# current_sense.net
KiCad netlist of a schematic drawn in Altium Designer
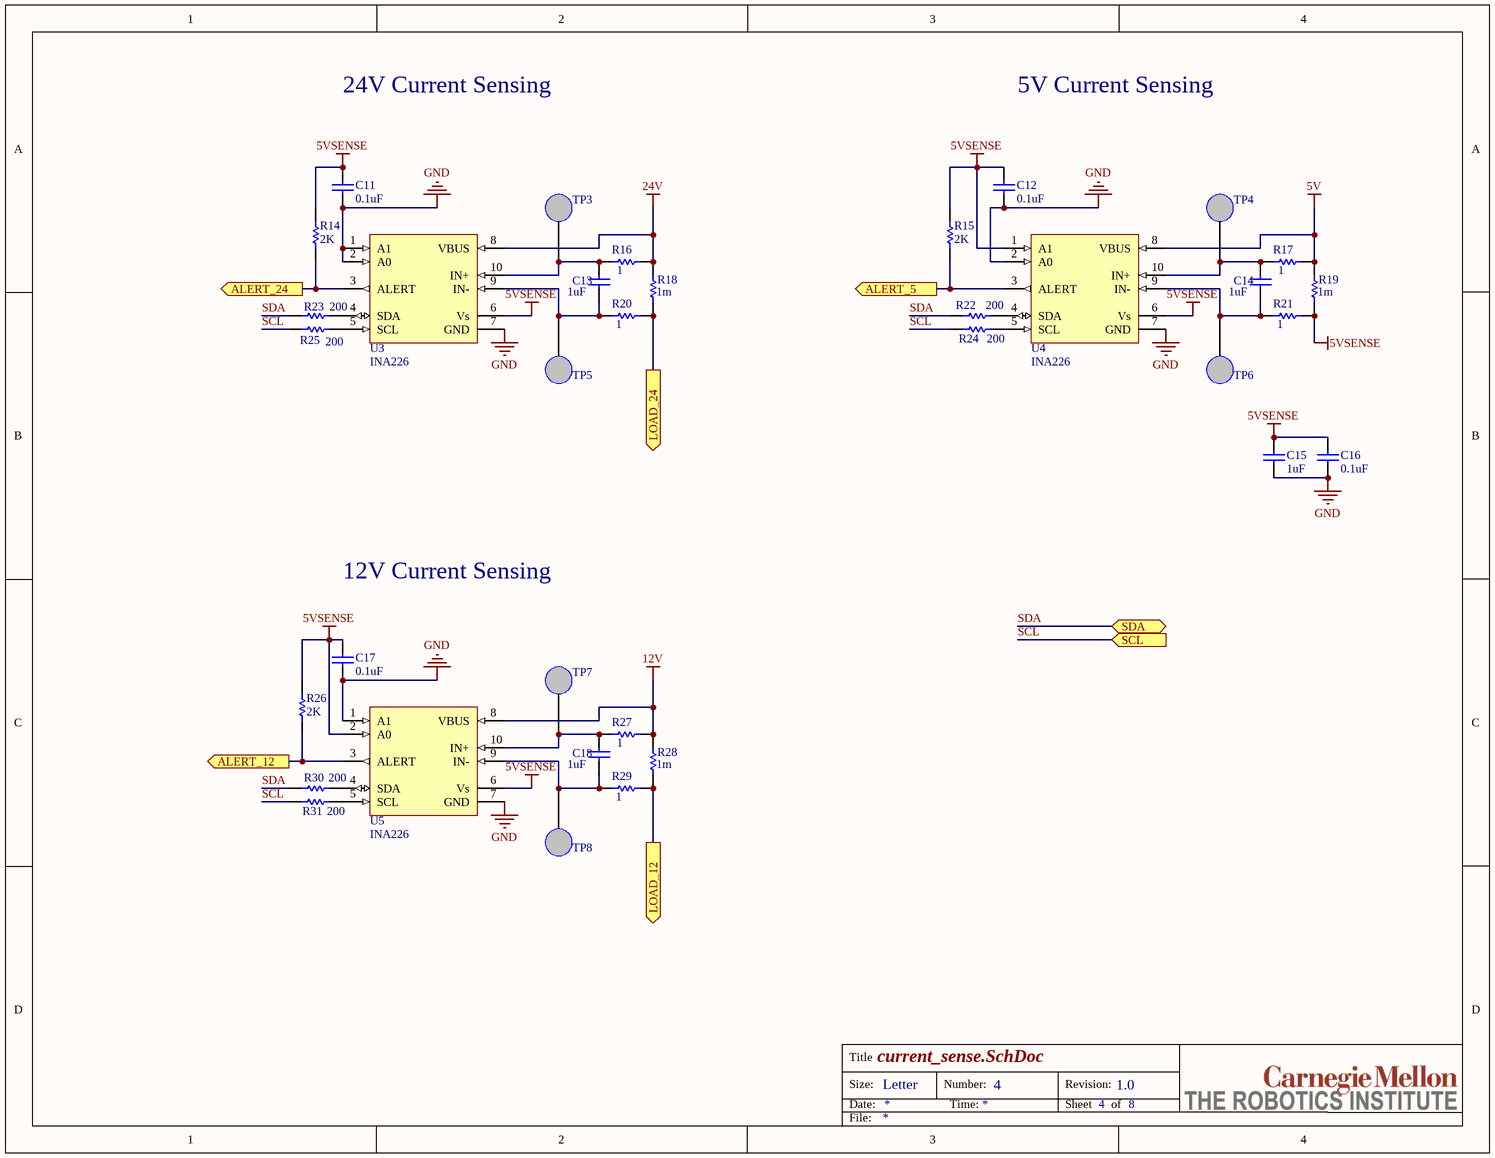
[diagram p0: current_sense.SchDoc]

(export (version "E")
  (design (tool "Eeschema 10.0.6"))
  (components
    (comp (ref "C11")
      (value "0.1uF")
      (footprint "CAPC1608N")
      (description "Capacitor")
      (fields
        (field (name "MANUFACTURER") "Murata Electronics North America")
        (field (name "MANUFACTURER PART NUMBER") "GRM188R71H104JA93D")
        (field (name "PUBLISHER") "Altium Limited")
      )
      (libsource (lib "Miscellaneous Devices") (part "Cap"))
    )
    (comp (ref "C12")
      (value "0.1uF")
      (footprint "CAPC1608N")
      (description "Capacitor")
      (fields
        (field (name "MANUFACTURER") "Murata Electronics North America")
        (field (name "MANUFACTURER PART NUMBER") "GRM188R71H104JA93D")
        (field (name "PUBLISHER") "Altium Limited")
      )
      (libsource (lib "Miscellaneous Devices") (part "Cap"))
    )
    (comp (ref "C13")
      (value "1uF")
      (footprint "CAPC1608N")
      (description "Capacitor")
      (fields
        (field (name "MANUFACTURER") "Murata Electronics North America")
        (field (name "MANUFACTURER PART NUMBER") "GRM188R61H105KAALD")
        (field (name "PUBLISHER") "Altium Limited")
      )
      (libsource (lib "Miscellaneous Devices") (part "Cap"))
    )
    (comp (ref "C14")
      (value "1uF")
      (footprint "CAPC1608N")
      (description "Capacitor")
      (fields
        (field (name "MANUFACTURER") "Murata Electronics North America")
        (field (name "MANUFACTURER PART NUMBER") "GRM188R61H105KAALD")
        (field (name "PUBLISHER") "Altium Limited")
      )
      (libsource (lib "Miscellaneous Devices") (part "Cap"))
    )
    (comp (ref "C15")
      (value "1uF")
      (footprint "CAPC1608N")
      (description "Capacitor")
      (fields
        (field (name "MANUFACTURER") "Murata Electronics North America")
        (field (name "MANUFACTURER PART NUMBER") "GRM188R61H105KAALD")
        (field (name "PUBLISHER") "Altium Limited")
      )
      (libsource (lib "Miscellaneous Devices") (part "Cap"))
    )
    (comp (ref "C16")
      (value "0.1uF")
      (footprint "CAPC1608N")
      (description "Capacitor")
      (fields
        (field (name "MANUFACTURER") "Murata Electronics North America")
        (field (name "MANUFACTURER PART NUMBER") "GRM188R71H104JA93D")
        (field (name "PUBLISHER") "Altium Limited")
      )
      (libsource (lib "Miscellaneous Devices") (part "Cap"))
    )
    (comp (ref "C17")
      (value "0.1uF")
      (footprint "CAPC1608N")
      (description "Capacitor")
      (fields
        (field (name "MANUFACTURER") "Murata Electronics North America")
        (field (name "MANUFACTURER PART NUMBER") "GRM188R71H104JA93D")
        (field (name "PUBLISHER") "Altium Limited")
      )
      (libsource (lib "Miscellaneous Devices") (part "Cap"))
    )
    (comp (ref "C18")
      (value "1uF")
      (footprint "CAPC1608N")
      (description "Capacitor")
      (fields
        (field (name "MANUFACTURER") "Murata Electronics North America")
        (field (name "MANUFACTURER PART NUMBER") "GRM188R61H105KAALD")
        (field (name "PUBLISHER") "Altium Limited")
      )
      (libsource (lib "Miscellaneous Devices") (part "Cap"))
    )
    (comp (ref "R14")
      (value "2K")
      (footprint "RESC1608N")
      (description "Resistor")
      (fields
        (field (name "MANUFACTURER") "Yageo")
        (field (name "MANUFACTURER PART NUMBER") "RC0603JR-072KL")
        (field (name "PUBLISHER") "Altium Limited")
      )
      (libsource (lib "Miscellaneous Devices") (part "Res1"))
    )
    (comp (ref "R15")
      (value "2K")
      (footprint "RESC1608N")
      (description "Resistor")
      (fields
        (field (name "MANUFACTURER") "Yageo")
        (field (name "MANUFACTURER PART NUMBER") "RC0603JR-072KL")
        (field (name "PUBLISHER") "Altium Limited")
      )
      (libsource (lib "Miscellaneous Devices") (part "Res1"))
    )
    (comp (ref "R16")
      (value "1")
      (footprint "RESC1608N")
      (description "Resistor")
      (fields
        (field (name "MANUFACTURER") "Yageo")
        (field (name "MANUFACTURER PART NUMBER") "RC0603FR-071RL")
        (field (name "PUBLISHER") "Altium Limited")
      )
      (libsource (lib "Miscellaneous Devices") (part "Res1"))
    )
    (comp (ref "R17")
      (value "1")
      (footprint "RESC1608N")
      (description "Resistor")
      (fields
        (field (name "MANUFACTURER") "Yageo")
        (field (name "MANUFACTURER PART NUMBER") "RC0603FR-071RL")
        (field (name "PUBLISHER") "Altium Limited")
      )
      (libsource (lib "Miscellaneous Devices") (part "Res1"))
    )
    (comp (ref "R18")
      (value "1m")
      (footprint "RES5931")
      (description "Resistor")
      (fields
        (field (name "MANUFACTURER") "Rohm Semiconductor")
        (field (name "MANUFACTURER PART NUMBER") "PSR500HTQFH1L00")
        (field (name "PUBLISHER") "Altium Limited")
      )
      (libsource (lib "Miscellaneous Devices") (part "Res1"))
    )
    (comp (ref "R19")
      (value "1m")
      (footprint "RESC3225N")
      (description "Resistor")
      (fields
        (field (name "MANUFACTURER") "Rohm Semiconductor")
        (field (name "MANUFACTURER PART NUMBER") "PMR25HZPFV1L00")
        (field (name "PUBLISHER") "Altium Limited")
      )
      (libsource (lib "Miscellaneous Devices") (part "Res1"))
    )
    (comp (ref "R20")
      (value "1")
      (footprint "RESC1608N")
      (description "Resistor")
      (fields
        (field (name "MANUFACTURER") "Yageo")
        (field (name "MANUFACTURER PART NUMBER") "RC0603FR-071RL")
        (field (name "PUBLISHER") "Altium Limited")
      )
      (libsource (lib "Miscellaneous Devices") (part "Res1"))
    )
    (comp (ref "R21")
      (value "1")
      (footprint "RESC1608N")
      (description "Resistor")
      (fields
        (field (name "MANUFACTURER") "Yageo")
        (field (name "MANUFACTURER PART NUMBER") "RC0603FR-071RL")
        (field (name "PUBLISHER") "Altium Limited")
      )
      (libsource (lib "Miscellaneous Devices") (part "Res1"))
    )
    (comp (ref "R22")
      (value "200")
      (footprint "RESC1608N")
      (description "Resistor")
      (fields
        (field (name "MANUFACTURER") "Yageo")
        (field (name "MANUFACTURER PART NUMBER") "RC0603JR-07200RL")
        (field (name "PUBLISHER") "Altium Limited")
      )
      (libsource (lib "Miscellaneous Devices") (part "Res1"))
    )
    (comp (ref "R23")
      (value "200")
      (footprint "RESC1608N")
      (description "Resistor")
      (fields
        (field (name "MANUFACTURER") "Yageo")
        (field (name "MANUFACTURER PART NUMBER") "RC0603JR-07200RL")
        (field (name "PUBLISHER") "Altium Limited")
      )
      (libsource (lib "Miscellaneous Devices") (part "Res1"))
    )
    (comp (ref "R24")
      (value "200")
      (footprint "RESC1608N")
      (description "Resistor")
      (fields
        (field (name "MANUFACTURER") "Yageo")
        (field (name "MANUFACTURER PART NUMBER") "RC0603JR-07200RL")
        (field (name "PUBLISHER") "Altium Limited")
      )
      (libsource (lib "Miscellaneous Devices") (part "Res1"))
    )
    (comp (ref "R25")
      (value "200")
      (footprint "RESC1608N")
      (description "Resistor")
      (fields
        (field (name "MANUFACTURER") "Yageo")
        (field (name "MANUFACTURER PART NUMBER") "RC0603JR-07200RL")
        (field (name "PUBLISHER") "Altium Limited")
      )
      (libsource (lib "Miscellaneous Devices") (part "Res1"))
    )
    (comp (ref "R26")
      (value "2K")
      (footprint "RESC1608N")
      (description "Resistor")
      (fields
        (field (name "MANUFACTURER") "Yageo")
        (field (name "MANUFACTURER PART NUMBER") "RC0603JR-072KL")
        (field (name "PUBLISHER") "Altium Limited")
      )
      (libsource (lib "Miscellaneous Devices") (part "Res1"))
    )
    (comp (ref "R27")
      (value "1")
      (footprint "RESC1608N")
      (description "Resistor")
      (fields
        (field (name "MANUFACTURER") "Yageo")
        (field (name "MANUFACTURER PART NUMBER") "RC0603FR-071RL")
        (field (name "PUBLISHER") "Altium Limited")
      )
      (libsource (lib "Miscellaneous Devices") (part "Res1"))
    )
    (comp (ref "R28")
      (value "1m")
      (footprint "RESC3225N")
      (description "Resistor")
      (fields
        (field (name "MANUFACTURER") "Rohm Semiconductor")
        (field (name "MANUFACTURER PART NUMBER") "PMR25HZPFV1L00")
        (field (name "PUBLISHER") "Altium Limited")
      )
      (libsource (lib "Miscellaneous Devices") (part "Res1"))
    )
    (comp (ref "R29")
      (value "1")
      (footprint "RESC1608N")
      (description "Resistor")
      (fields
        (field (name "MANUFACTURER") "Yageo")
        (field (name "MANUFACTURER PART NUMBER") "RC0603FR-071RL")
        (field (name "PUBLISHER") "Altium Limited")
      )
      (libsource (lib "Miscellaneous Devices") (part "Res1"))
    )
    (comp (ref "R30")
      (value "200")
      (footprint "RESC1608N")
      (description "Resistor")
      (fields
        (field (name "MANUFACTURER") "Yageo")
        (field (name "MANUFACTURER PART NUMBER") "RC0603JR-07200RL")
        (field (name "PUBLISHER") "Altium Limited")
      )
      (libsource (lib "Miscellaneous Devices") (part "Res1"))
    )
    (comp (ref "R31")
      (value "200")
      (footprint "RESC1608N")
      (description "Resistor")
      (fields
        (field (name "MANUFACTURER") "Yageo")
        (field (name "MANUFACTURER PART NUMBER") "RC0603JR-07200RL")
        (field (name "PUBLISHER") "Altium Limited")
      )
      (libsource (lib "Miscellaneous Devices") (part "Res1"))
    )
    (comp (ref "TP3")
      (value "LOAD")
      (footprint "TestPoint")
      (description "Test Point")
      (libsource (lib "common") (part "Ring_Terminal"))
    )
    (comp (ref "TP4")
      (value "SUPPLY")
      (footprint "TestPoint")
      (description "Test Point")
      (libsource (lib "common") (part "Ring_Terminal"))
    )
    (comp (ref "TP5")
      (value "SUPPLY")
      (footprint "TestPoint")
      (description "Test Point")
      (libsource (lib "common") (part "Ring_Terminal"))
    )
    (comp (ref "TP6")
      (value "LOAD")
      (footprint "TestPoint")
      (description "Test Point")
      (libsource (lib "common") (part "Ring_Terminal"))
    )
    (comp (ref "TP7")
      (value "SUPPLY")
      (footprint "TestPoint")
      (description "Test Point")
      (libsource (lib "common") (part "Ring_Terminal"))
    )
    (comp (ref "TP8")
      (value "LOAD")
      (footprint "TestPoint")
      (description "Test Point")
      (libsource (lib "common") (part "Ring_Terminal"))
    )
    (comp (ref "U3")
      (value "INA226")
      (footprint "10-VSSOP")
      (description "Current Shunt Monitor - I2C Interface")
      (fields
        (field (name "MANUFACTURER") "Texas Instruments")
        (field (name "MANUFACTURER PART NUMBER") "INA226AIDGSR")
      )
      (libsource (lib "common") (part "INA226"))
    )
    (comp (ref "U4")
      (value "INA226")
      (footprint "10-VSSOP")
      (description "Current Shunt Monitor - I2C Interface")
      (fields
        (field (name "MANUFACTURER") "Texas Instruments")
        (field (name "MANUFACTURER PART NUMBER") "INA226AIDGSR")
      )
      (libsource (lib "common") (part "INA226"))
    )
    (comp (ref "U5")
      (value "INA226")
      (footprint "10-VSSOP")
      (description "Current Shunt Monitor - I2C Interface")
      (fields
        (field (name "MANUFACTURER") "Texas Instruments")
        (field (name "MANUFACTURER PART NUMBER") "INA226AIDGSR")
      )
      (libsource (lib "common") (part "INA226"))
    )
  )
  (nets
    (net (code "1") (name "/ALERT_5") (class "Default")
      (node (ref "R15") (pin "2") (pinfunction "2_2") (pintype "passive"))
      (node (ref "U4") (pin "3") (pinfunction "ALERT_3") (pintype "output"))
    )
    (net (code "2") (name "/ALERT_12") (class "Default")
      (node (ref "R26") (pin "2") (pinfunction "2_2") (pintype "passive"))
      (node (ref "U5") (pin "3") (pinfunction "ALERT_3") (pintype "output"))
    )
    (net (code "3") (name "/ALERT_24") (class "Default")
      (node (ref "R14") (pin "2") (pinfunction "2_2") (pintype "passive"))
      (node (ref "U3") (pin "3") (pinfunction "ALERT_3") (pintype "output"))
    )
    (net (code "4") (name "/LOAD_12") (class "Default")
      (node (ref "R28") (pin "1") (pinfunction "1_1") (pintype "passive"))
      (node (ref "R29") (pin "1") (pinfunction "1_1") (pintype "passive"))
    )
    (net (code "5") (name "/LOAD_24") (class "Default")
      (node (ref "R18") (pin "1") (pinfunction "1_1") (pintype "passive"))
      (node (ref "R20") (pin "1") (pinfunction "1_1") (pintype "passive"))
    )
    (net (code "6") (name "/SCL") (class "Default")
      (node (ref "R24") (pin "2") (pinfunction "2_2") (pintype "passive"))
      (node (ref "R25") (pin "2") (pinfunction "2_2") (pintype "passive"))
      (node (ref "R31") (pin "2") (pinfunction "2_2") (pintype "passive"))
    )
    (net (code "7") (name "/SDA") (class "Default")
      (node (ref "R22") (pin "2") (pinfunction "2_2") (pintype "passive"))
      (node (ref "R23") (pin "2") (pinfunction "2_2") (pintype "passive"))
      (node (ref "R30") (pin "2") (pinfunction "2_2") (pintype "passive"))
    )
    (net (code "8") (name "5V") (class "Default")
      (node (ref "R17") (pin "1") (pinfunction "1_1") (pintype "passive"))
      (node (ref "R19") (pin "2") (pinfunction "2_2") (pintype "passive"))
      (node (ref "U4") (pin "8") (pinfunction "VBUS_8") (pintype "input"))
    )
    (net (code "9") (name "5VSENSE") (class "Default")
      (node (ref "C11") (pin "2") (pinfunction "2_2") (pintype "passive"))
      (node (ref "C12") (pin "2") (pinfunction "2_2") (pintype "passive"))
      (node (ref "C15") (pin "2") (pinfunction "2_2") (pintype "passive"))
      (node (ref "C16") (pin "2") (pinfunction "2_2") (pintype "passive"))
      (node (ref "C17") (pin "2") (pinfunction "2_2") (pintype "passive"))
      (node (ref "R14") (pin "1") (pinfunction "1_1") (pintype "passive"))
      (node (ref "R15") (pin "1") (pinfunction "1_1") (pintype "passive"))
      (node (ref "R19") (pin "1") (pinfunction "1_1") (pintype "passive"))
      (node (ref "R21") (pin "1") (pinfunction "1_1") (pintype "passive"))
      (node (ref "R26") (pin "1") (pinfunction "1_1") (pintype "passive"))
      (node (ref "U3") (pin "6") (pinfunction "Vs_6") (pintype "power_in"))
      (node (ref "U4") (pin "1") (pinfunction "A1_1") (pintype "input"))
      (node (ref "U4") (pin "6") (pinfunction "Vs_6") (pintype "power_in"))
      (node (ref "U5") (pin "2") (pinfunction "A0_2") (pintype "input"))
      (node (ref "U5") (pin "6") (pinfunction "Vs_6") (pintype "power_in"))
    )
    (net (code "10") (name "12V") (class "Default")
      (node (ref "R27") (pin "1") (pinfunction "1_1") (pintype "passive"))
      (node (ref "R28") (pin "2") (pinfunction "2_2") (pintype "passive"))
      (node (ref "U5") (pin "8") (pinfunction "VBUS_8") (pintype "input"))
    )
    (net (code "11") (name "24V") (class "Default")
      (node (ref "R16") (pin "1") (pinfunction "1_1") (pintype "passive"))
      (node (ref "R18") (pin "2") (pinfunction "2_2") (pintype "passive"))
      (node (ref "U3") (pin "8") (pinfunction "VBUS_8") (pintype "input"))
    )
    (net (code "12") (name "GND") (class "Default")
      (node (ref "C11") (pin "1") (pinfunction "1_1") (pintype "passive"))
      (node (ref "C12") (pin "1") (pinfunction "1_1") (pintype "passive"))
      (node (ref "C15") (pin "1") (pinfunction "1_1") (pintype "passive"))
      (node (ref "C16") (pin "1") (pinfunction "1_1") (pintype "passive"))
      (node (ref "C17") (pin "1") (pinfunction "1_1") (pintype "passive"))
      (node (ref "U3") (pin "1") (pinfunction "A1_1") (pintype "input"))
      (node (ref "U3") (pin "2") (pinfunction "A0_2") (pintype "input"))
      (node (ref "U3") (pin "7") (pinfunction "GND_7") (pintype "power_in"))
      (node (ref "U4") (pin "2") (pinfunction "A0_2") (pintype "input"))
      (node (ref "U4") (pin "7") (pinfunction "GND_7") (pintype "power_in"))
      (node (ref "U5") (pin "1") (pinfunction "A1_1") (pintype "input"))
      (node (ref "U5") (pin "7") (pinfunction "GND_7") (pintype "power_in"))
    )
    (net (code "13") (name "Net-(U3-IN+)") (class "Default")
      (node (ref "C13") (pin "1") (pinfunction "1_1") (pintype "passive"))
      (node (ref "R16") (pin "2") (pinfunction "2_2") (pintype "passive"))
      (node (ref "TP3") (pin "1") (pinfunction "1_1") (pintype "passive"))
      (node (ref "U3") (pin "10") (pinfunction "IN+_10") (pintype "input"))
    )
    (net (code "14") (name "Net-(U3-IN-)") (class "Default")
      (node (ref "C13") (pin "2") (pinfunction "2_2") (pintype "passive"))
      (node (ref "R20") (pin "2") (pinfunction "2_2") (pintype "passive"))
      (node (ref "TP5") (pin "1") (pinfunction "1_1") (pintype "passive"))
      (node (ref "U3") (pin "9") (pinfunction "IN-_9") (pintype "input"))
    )
    (net (code "15") (name "Net-(U3-SCL)") (class "Default")
      (node (ref "R25") (pin "1") (pinfunction "1_1") (pintype "passive"))
      (node (ref "U3") (pin "5") (pinfunction "SCL_5") (pintype "input"))
    )
    (net (code "16") (name "Net-(U3-SDA)") (class "Default")
      (node (ref "R23") (pin "1") (pinfunction "1_1") (pintype "passive"))
      (node (ref "U3") (pin "4") (pinfunction "SDA_4") (pintype "bidirectional"))
    )
    (net (code "17") (name "Net-(U4-IN+)") (class "Default")
      (node (ref "C14") (pin "1") (pinfunction "1_1") (pintype "passive"))
      (node (ref "R17") (pin "2") (pinfunction "2_2") (pintype "passive"))
      (node (ref "TP4") (pin "1") (pinfunction "1_1") (pintype "passive"))
      (node (ref "U4") (pin "10") (pinfunction "IN+_10") (pintype "input"))
    )
    (net (code "18") (name "Net-(U4-IN-)") (class "Default")
      (node (ref "C14") (pin "2") (pinfunction "2_2") (pintype "passive"))
      (node (ref "R21") (pin "2") (pinfunction "2_2") (pintype "passive"))
      (node (ref "TP6") (pin "1") (pinfunction "1_1") (pintype "passive"))
      (node (ref "U4") (pin "9") (pinfunction "IN-_9") (pintype "input"))
    )
    (net (code "19") (name "Net-(U4-SCL)") (class "Default")
      (node (ref "R24") (pin "1") (pinfunction "1_1") (pintype "passive"))
      (node (ref "U4") (pin "5") (pinfunction "SCL_5") (pintype "input"))
    )
    (net (code "20") (name "Net-(U4-SDA)") (class "Default")
      (node (ref "R22") (pin "1") (pinfunction "1_1") (pintype "passive"))
      (node (ref "U4") (pin "4") (pinfunction "SDA_4") (pintype "bidirectional"))
    )
    (net (code "21") (name "Net-(U5-IN+)") (class "Default")
      (node (ref "C18") (pin "1") (pinfunction "1_1") (pintype "passive"))
      (node (ref "R27") (pin "2") (pinfunction "2_2") (pintype "passive"))
      (node (ref "TP7") (pin "1") (pinfunction "1_1") (pintype "passive"))
      (node (ref "U5") (pin "10") (pinfunction "IN+_10") (pintype "input"))
    )
    (net (code "22") (name "Net-(U5-IN-)") (class "Default")
      (node (ref "C18") (pin "2") (pinfunction "2_2") (pintype "passive"))
      (node (ref "R29") (pin "2") (pinfunction "2_2") (pintype "passive"))
      (node (ref "TP8") (pin "1") (pinfunction "1_1") (pintype "passive"))
      (node (ref "U5") (pin "9") (pinfunction "IN-_9") (pintype "input"))
    )
    (net (code "23") (name "Net-(U5-SCL)") (class "Default")
      (node (ref "R31") (pin "1") (pinfunction "1_1") (pintype "passive"))
      (node (ref "U5") (pin "5") (pinfunction "SCL_5") (pintype "input"))
    )
    (net (code "24") (name "Net-(U5-SDA)") (class "Default")
      (node (ref "R30") (pin "1") (pinfunction "1_1") (pintype "passive"))
      (node (ref "U5") (pin "4") (pinfunction "SDA_4") (pintype "bidirectional"))
    )
  )
)
